# Signal_Turn_YBR_Front.net
KiCad netlist of a schematic drawn in Altium Designer
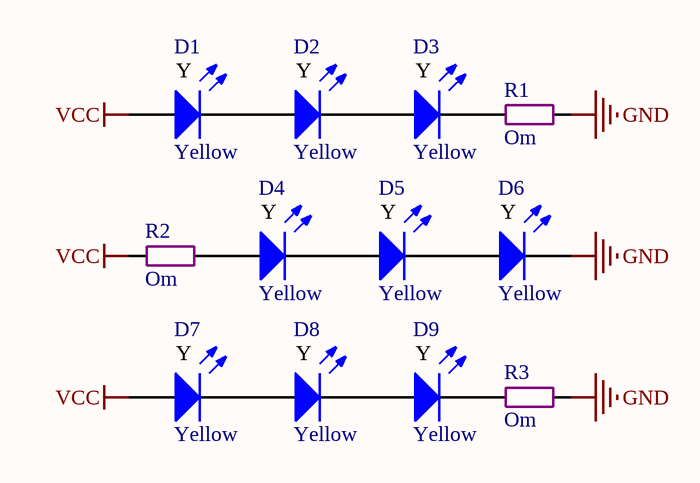
[diagram p0: Signal Turn YBR Front.SchDoc]

(export (version "E")
  (design (tool "Eeschema 10.0.6"))
  (components
    (comp (ref "D1")
      (value "Yellow")
      (footprint "LED:LED Round 8mm Yellow")
      (description "2.8-3v 25mA, 4-5cd")
      (libsource (lib "LED") (part "Led Round 8mm Yellow 0.5W"))
    )
    (comp (ref "D2")
      (value "Yellow")
      (footprint "LED:LED Round 8mm Yellow")
      (description "2.8-3v 25mA, 4-5cd")
      (libsource (lib "LED") (part "Led Round 8mm Yellow 0.5W"))
    )
    (comp (ref "D3")
      (value "Yellow")
      (footprint "LED:LED Round 8mm Yellow")
      (description "2.8-3v 25mA, 4-5cd")
      (libsource (lib "LED") (part "Led Round 8mm Yellow 0.5W"))
    )
    (comp (ref "D4")
      (value "Yellow")
      (footprint "LED:LED Round 8mm Yellow")
      (description "2.8-3v 25mA, 4-5cd")
      (libsource (lib "LED") (part "Led Round 8mm Yellow 0.5W"))
    )
    (comp (ref "D5")
      (value "Yellow")
      (footprint "LED:LED Round 8mm Yellow")
      (description "2.8-3v 25mA, 4-5cd")
      (libsource (lib "LED") (part "Led Round 8mm Yellow 0.5W"))
    )
    (comp (ref "D6")
      (value "Yellow")
      (footprint "LED:LED Round 8mm Yellow")
      (description "2.8-3v 25mA, 4-5cd")
      (libsource (lib "LED") (part "Led Round 8mm Yellow 0.5W"))
    )
    (comp (ref "D7")
      (value "Yellow")
      (footprint "LED:LED Round 8mm Yellow")
      (description "2.8-3v 25mA, 4-5cd")
      (libsource (lib "LED") (part "Led Round 8mm Yellow 0.5W"))
    )
    (comp (ref "D8")
      (value "Yellow")
      (footprint "LED:LED Round 8mm Yellow")
      (description "2.8-3v 25mA, 4-5cd")
      (libsource (lib "LED") (part "Led Round 8mm Yellow 0.5W"))
    )
    (comp (ref "D9")
      (value "Yellow")
      (footprint "LED:LED Round 8mm Yellow")
      (description "2.8-3v 25mA, 4-5cd")
      (libsource (lib "LED") (part "Led Round 8mm Yellow 0.5W"))
    )
    (comp (ref "R1")
      (value "Om")
      (footprint "PassiveComponents:Res p20.32 (9p) 2w")
      (description "5W Cement")
      (libsource (lib "PassiveComponents") (part "Res 2W"))
    )
    (comp (ref "R2")
      (value "Om")
      (footprint "PassiveComponents:Res p20.32 (9p) 2w")
      (description "5W Cement")
      (libsource (lib "PassiveComponents") (part "Res 2W"))
    )
    (comp (ref "R3")
      (value "Om")
      (footprint "PassiveComponents:Res p20.32 (9p) 2w")
      (description "5W Cement")
      (libsource (lib "PassiveComponents") (part "Res 2W"))
    )
  )
  (nets
    (net (code "1") (name "GND") (class "Default")
      (node (ref "D6") (pin "K") (pinfunction "K_K") (pintype "passive"))
      (node (ref "R1") (pin "2") (pinfunction "2_2") (pintype "passive"))
      (node (ref "R3") (pin "2") (pinfunction "2_2") (pintype "passive"))
    )
    (net (code "2") (name "Net-(D1-PadK)") (class "Default")
      (node (ref "D1") (pin "K") (pinfunction "K_K") (pintype "passive"))
      (node (ref "D2") (pin "A") (pinfunction "A_A") (pintype "passive"))
    )
    (net (code "3") (name "Net-(D2-PadK)") (class "Default")
      (node (ref "D2") (pin "K") (pinfunction "K_K") (pintype "passive"))
      (node (ref "D3") (pin "A") (pinfunction "A_A") (pintype "passive"))
    )
    (net (code "4") (name "Net-(D3-PadK)") (class "Default")
      (node (ref "D3") (pin "K") (pinfunction "K_K") (pintype "passive"))
      (node (ref "R1") (pin "1") (pinfunction "1_1") (pintype "passive"))
    )
    (net (code "5") (name "Net-(D4-PadA)") (class "Default")
      (node (ref "D4") (pin "A") (pinfunction "A_A") (pintype "passive"))
      (node (ref "R2") (pin "2") (pinfunction "2_2") (pintype "passive"))
    )
    (net (code "6") (name "Net-(D4-PadK)") (class "Default")
      (node (ref "D4") (pin "K") (pinfunction "K_K") (pintype "passive"))
      (node (ref "D5") (pin "A") (pinfunction "A_A") (pintype "passive"))
    )
    (net (code "7") (name "Net-(D5-PadK)") (class "Default")
      (node (ref "D5") (pin "K") (pinfunction "K_K") (pintype "passive"))
      (node (ref "D6") (pin "A") (pinfunction "A_A") (pintype "passive"))
    )
    (net (code "8") (name "Net-(D7-PadK)") (class "Default")
      (node (ref "D7") (pin "K") (pinfunction "K_K") (pintype "passive"))
      (node (ref "D8") (pin "A") (pinfunction "A_A") (pintype "passive"))
    )
    (net (code "9") (name "Net-(D8-PadK)") (class "Default")
      (node (ref "D8") (pin "K") (pinfunction "K_K") (pintype "passive"))
      (node (ref "D9") (pin "A") (pinfunction "A_A") (pintype "passive"))
    )
    (net (code "10") (name "Net-(D9-PadK)") (class "Default")
      (node (ref "D9") (pin "K") (pinfunction "K_K") (pintype "passive"))
      (node (ref "R3") (pin "1") (pinfunction "1_1") (pintype "passive"))
    )
    (net (code "11") (name "VCC") (class "Default")
      (node (ref "D1") (pin "A") (pinfunction "A_A") (pintype "passive"))
      (node (ref "D7") (pin "A") (pinfunction "A_A") (pintype "passive"))
      (node (ref "R2") (pin "1") (pinfunction "1_1") (pintype "passive"))
    )
  )
)
